# boot.net
KiCad netlist of a schematic drawn in EAGLE
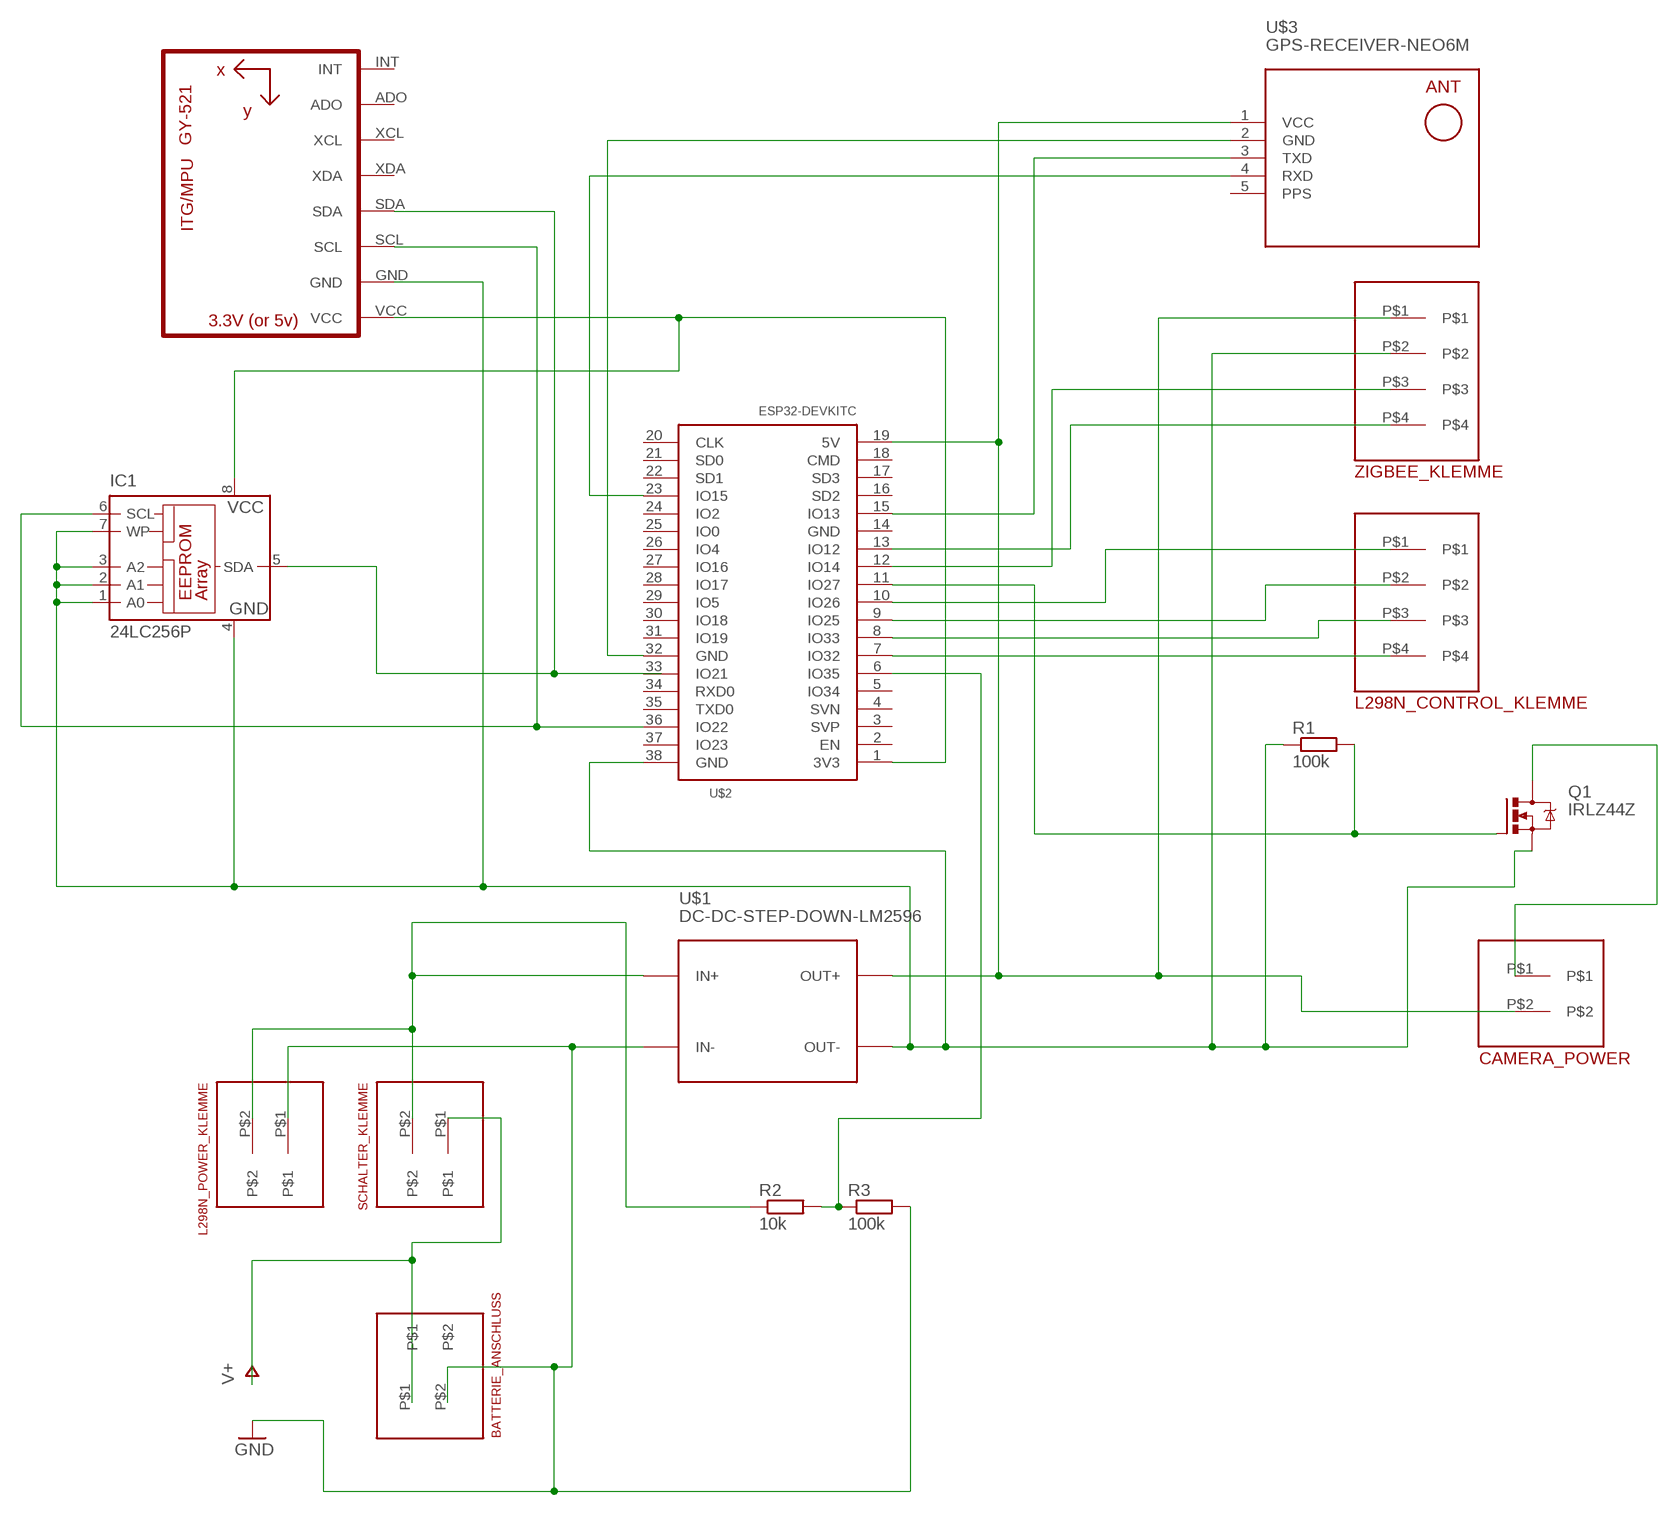
[diagram p0: schematic, sheet 1]

(export (version "E")
  (design (tool "Eeschema 10.0.6"))
  (components
    (comp (ref "BATTERIE_ANSCHLUSS")
      (value "SCHRAUBKLEMME_X_2RM5.08")
      (footprint "eagle-import:2_PIN_RM5.08")
      (libsource (lib "eagle-import") (part "SCHRAUBKLEMME_X_2RM5.08"))
    )
    (comp (ref "CAMERA_POWER")
      (value "AKL_349_X2")
      (footprint "eagle-import:2_PIN_AKL_349_BUCHSE")
      (libsource (lib "eagle-import") (part "AKL_349_X2"))
    )
    (comp (ref "IC1")
      (value "24LC256P")
      (footprint "eagle-import:DIL8")
      (fields (field (name "MF") "MICROCHIP") (field (name "MPN") "24LC256-E/P"))
      (libsource (lib "eagle-import") (part "24PLC256"))
    )
    (comp (ref "L298N_CONTROL_KLEMME")
      (value "SCHRAUBKLEMME_X_4")
      (footprint "eagle-import:4_PIN_RM5.08_SCHRAUBKLEMME")
      (libsource (lib "eagle-import") (part "SCHRAUBKLEMME_X_4"))
    )
    (comp (ref "L298N_POWER_KLEMME")
      (value "SCHRAUBKLEMME_X_2RM5.08")
      (footprint "eagle-import:2_PIN_RM5.08")
      (libsource (lib "eagle-import") (part "SCHRAUBKLEMME_X_2RM5.08"))
    )
    (comp (ref "Q1")
      (value "IRLZ44Z")
      (footprint "eagle-import:TO220BH")
      (libsource (lib "eagle-import") (part "IRLZ44Z"))
    )
    (comp (ref "R1")
      (value "100k")
      (footprint "eagle-import:0207_7")
      (libsource (lib "eagle-import") (part "R-EU_0207/7"))
    )
    (comp (ref "R2")
      (value "10k")
      (footprint "eagle-import:0207_7")
      (libsource (lib "eagle-import") (part "R-EU_0207/7"))
    )
    (comp (ref "R3")
      (value "100k")
      (footprint "eagle-import:0207_7")
      (libsource (lib "eagle-import") (part "R-EU_0207/7"))
    )
    (comp (ref "SCHALTER_KLEMME")
      (value "SCHRAUBKLEMME_X_2RM5.08")
      (footprint "eagle-import:2_PIN_RM5.08")
      (libsource (lib "eagle-import") (part "SCHRAUBKLEMME_X_2RM5.08"))
    )
    (comp (ref "U$1")
      (value "DC-DC-STEP-DOWN-LM2596")
      (footprint "eagle-import:DC-DC-STEP-DOWN-LM2596")
      (libsource (lib "eagle-import") (part "DC-DC-STEP-DOWN-LM2596"))
    )
    (comp (ref "U$2")
      (value "ESP32DEVKITC")
      (footprint "eagle-import:ESP32-DEVKITC")
      (libsource (lib "eagle-import") (part "ESP32DEVKITC"))
    )
    (comp (ref "U$3")
      (value "GPS-RECEIVER-NEO6M")
      (footprint "eagle-import:GPS-RECEIVER-NEO6M")
      (libsource (lib "eagle-import") (part "GPS-RECEIVER-NEO6M"))
    )
    (comp (ref "U1")
      (value "GY-521MPU6050")
      (footprint "eagle-import:GY-521")
      (libsource (lib "eagle-import") (part "GY-521MPU6050"))
    )
    (comp (ref "ZIGBEE_KLEMME")
      (value "SCHRAUBKLEMME_X_4")
      (footprint "eagle-import:4_PIN_RM5.08_SCHRAUBKLEMME")
      (libsource (lib "eagle-import") (part "SCHRAUBKLEMME_X_4"))
    )
  )
  (nets
    (net (code "1") (name "/PPS") (class "Default")
      (node (ref "U$3") (pin "5") (pinfunction "PPS_5") (pintype "power_in"))
    )
    (net (code "2") (name "GND") (class "Default")
      (node (ref "BATTERIE_ANSCHLUSS") (pin "P$2") (pinfunction "P$2_P$2") (pintype "bidirectional"))
      (node (ref "L298N_POWER_KLEMME") (pin "P$1") (pinfunction "P$1_P$1") (pintype "bidirectional"))
      (node (ref "R3") (pin "2") (pinfunction "2_2") (pintype "passive"))
      (node (ref "U$1") (pin "IN-") (pinfunction "IN-_IN-") (pintype "bidirectional"))
    )
    (net (code "3") (name "Net-(CAMERA_POWER-PadP$1)") (class "Default")
      (node (ref "CAMERA_POWER") (pin "P$1") (pinfunction "P$1_P$1") (pintype "bidirectional"))
      (node (ref "Q1") (pin "D") (pinfunction "D_D") (pintype "passive"))
    )
    (net (code "4") (name "Net-(IC1-A0)") (class "Default")
      (node (ref "IC1") (pin "1") (pinfunction "A0_1") (pintype "input"))
      (node (ref "IC1") (pin "2") (pinfunction "A1_2") (pintype "input"))
      (node (ref "IC1") (pin "3") (pinfunction "A2_3") (pintype "input"))
      (node (ref "IC1") (pin "4") (pinfunction "GND_4") (pintype "power_in"))
      (node (ref "IC1") (pin "7") (pinfunction "WP_7") (pintype "input"))
      (node (ref "Q1") (pin "S") (pinfunction "S_S") (pintype "passive"))
      (node (ref "R1") (pin "1") (pinfunction "1_1") (pintype "passive"))
      (node (ref "U$1") (pin "OUT-") (pinfunction "OUT-_OUT-") (pintype "bidirectional"))
      (node (ref "U$2") (pin "38") (pinfunction "GND_38") (pintype "bidirectional"))
      (node (ref "U1") (pin "GND") (pinfunction "GND_GND") (pintype "bidirectional"))
      (node (ref "ZIGBEE_KLEMME") (pin "P$2") (pinfunction "P$2_P$2") (pintype "bidirectional"))
    )
    (net (code "5") (name "Net-(IC1-SCL)") (class "Default")
      (node (ref "IC1") (pin "6") (pinfunction "SCL_6") (pintype "input"))
      (node (ref "U$2") (pin "36") (pinfunction "IO22_36") (pintype "bidirectional"))
      (node (ref "U1") (pin "SCL") (pinfunction "SCL_SCL") (pintype "bidirectional"))
    )
    (net (code "6") (name "Net-(IC1-SDA)") (class "Default")
      (node (ref "IC1") (pin "5") (pinfunction "SDA_5") (pintype "bidirectional"))
      (node (ref "U1") (pin "SDA") (pinfunction "SDA_SDA") (pintype "bidirectional"))
    )
    (net (code "7") (name "Net-(IC1-VCC)") (class "Default")
      (node (ref "IC1") (pin "8") (pinfunction "VCC_8") (pintype "power_in"))
      (node (ref "U$2") (pin "1") (pinfunction "3V3_1") (pintype "bidirectional"))
      (node (ref "U1") (pin "VCC") (pinfunction "VCC_VCC") (pintype "bidirectional"))
    )
    (net (code "8") (name "Net-(L298N_POWER_KLEMME-PadP$2)") (class "Default")
      (node (ref "L298N_POWER_KLEMME") (pin "P$2") (pinfunction "P$2_P$2") (pintype "bidirectional"))
      (node (ref "R2") (pin "1") (pinfunction "1_1") (pintype "passive"))
      (node (ref "SCHALTER_KLEMME") (pin "P$2") (pinfunction "P$2_P$2") (pintype "bidirectional"))
      (node (ref "U$1") (pin "IN+") (pinfunction "IN+_IN+") (pintype "bidirectional"))
    )
    (net (code "9") (name "Net-(U$2-5V)") (class "Default")
      (node (ref "CAMERA_POWER") (pin "P$2") (pinfunction "P$2_P$2") (pintype "bidirectional"))
      (node (ref "U$1") (pin "OUT+") (pinfunction "OUT+_OUT+") (pintype "bidirectional"))
      (node (ref "U$2") (pin "19") (pinfunction "5V_19") (pintype "bidirectional"))
      (node (ref "U$3") (pin "1") (pinfunction "VCC_1") (pintype "bidirectional"))
      (node (ref "ZIGBEE_KLEMME") (pin "P$1") (pinfunction "P$1_P$1") (pintype "bidirectional"))
    )
    (net (code "10") (name "Net-(U$2-IO12)") (class "Default")
      (node (ref "U$2") (pin "13") (pinfunction "IO12_13") (pintype "bidirectional"))
      (node (ref "ZIGBEE_KLEMME") (pin "P$4") (pinfunction "P$4_P$4") (pintype "bidirectional"))
    )
    (net (code "11") (name "Net-(U$2-IO13)") (class "Default")
      (node (ref "U$2") (pin "15") (pinfunction "IO13_15") (pintype "bidirectional"))
      (node (ref "U$3") (pin "3") (pinfunction "TXD_3") (pintype "bidirectional"))
    )
    (net (code "12") (name "Net-(U$2-IO14)") (class "Default")
      (node (ref "U$2") (pin "12") (pinfunction "IO14_12") (pintype "bidirectional"))
      (node (ref "ZIGBEE_KLEMME") (pin "P$3") (pinfunction "P$3_P$3") (pintype "bidirectional"))
    )
    (net (code "13") (name "Net-(U$2-IO15)") (class "Default")
      (node (ref "U$2") (pin "23") (pinfunction "IO15_23") (pintype "bidirectional"))
      (node (ref "U$3") (pin "4") (pinfunction "RXD_4") (pintype "power_in"))
    )
    (net (code "14") (name "Net-(U$2-IO25)") (class "Default")
      (node (ref "L298N_CONTROL_KLEMME") (pin "P$2") (pinfunction "P$2_P$2") (pintype "bidirectional"))
      (node (ref "U$2") (pin "9") (pinfunction "IO25_9") (pintype "bidirectional"))
    )
    (net (code "15") (name "Net-(U$2-IO26)") (class "Default")
      (node (ref "L298N_CONTROL_KLEMME") (pin "P$1") (pinfunction "P$1_P$1") (pintype "bidirectional"))
      (node (ref "U$2") (pin "10") (pinfunction "IO26_10") (pintype "bidirectional"))
    )
    (net (code "16") (name "Net-(U$2-IO27)") (class "Default")
      (node (ref "Q1") (pin "G") (pinfunction "G_G") (pintype "passive"))
      (node (ref "R1") (pin "2") (pinfunction "2_2") (pintype "passive"))
      (node (ref "U$2") (pin "11") (pinfunction "IO27_11") (pintype "bidirectional"))
    )
    (net (code "17") (name "Net-(U$2-IO32)") (class "Default")
      (node (ref "L298N_CONTROL_KLEMME") (pin "P$4") (pinfunction "P$4_P$4") (pintype "bidirectional"))
      (node (ref "U$2") (pin "7") (pinfunction "IO32_7") (pintype "bidirectional"))
    )
    (net (code "18") (name "Net-(U$2-IO33)") (class "Default")
      (node (ref "L298N_CONTROL_KLEMME") (pin "P$3") (pinfunction "P$3_P$3") (pintype "bidirectional"))
      (node (ref "U$2") (pin "8") (pinfunction "IO33_8") (pintype "bidirectional"))
    )
    (net (code "19") (name "Net-(U$2-IO35)") (class "Default")
      (node (ref "R2") (pin "2") (pinfunction "2_2") (pintype "passive"))
      (node (ref "R3") (pin "1") (pinfunction "1_1") (pintype "passive"))
      (node (ref "U$2") (pin "6") (pinfunction "IO35_6") (pintype "bidirectional"))
    )
    (net (code "20") (name "Net-(U$3-GND)") (class "Default")
      (node (ref "U$2") (pin "32") (pinfunction "GND_32") (pintype "bidirectional"))
      (node (ref "U$3") (pin "2") (pinfunction "GND_2") (pintype "bidirectional"))
    )
    (net (code "21") (name "V+") (class "Default")
      (node (ref "BATTERIE_ANSCHLUSS") (pin "P$1") (pinfunction "P$1_P$1") (pintype "bidirectional"))
      (node (ref "SCHALTER_KLEMME") (pin "P$1") (pinfunction "P$1_P$1") (pintype "bidirectional"))
    )
    (net (code "22") (name "unconnected-(U$2-CLK-Pad20)") (class "Default")
      (node (ref "U$2") (pin "20") (pinfunction "CLK_20") (pintype "bidirectional"))
    )
    (net (code "23") (name "unconnected-(U$2-CMD-Pad18)") (class "Default")
      (node (ref "U$2") (pin "18") (pinfunction "CMD_18") (pintype "bidirectional"))
    )
    (net (code "24") (name "unconnected-(U$2-EN-Pad2)") (class "Default")
      (node (ref "U$2") (pin "2") (pinfunction "EN_2") (pintype "bidirectional"))
    )
    (net (code "25") (name "unconnected-(U$2-GND-Pad14)") (class "Default")
      (node (ref "U$2") (pin "14") (pinfunction "GND_14") (pintype "bidirectional"))
    )
    (net (code "26") (name "unconnected-(U$2-IO0-Pad25)") (class "Default")
      (node (ref "U$2") (pin "25") (pinfunction "IO0_25") (pintype "bidirectional"))
    )
    (net (code "27") (name "unconnected-(U$2-IO2-Pad24)") (class "Default")
      (node (ref "U$2") (pin "24") (pinfunction "IO2_24") (pintype "bidirectional"))
    )
    (net (code "28") (name "unconnected-(U$2-IO4-Pad26)") (class "Default")
      (node (ref "U$2") (pin "26") (pinfunction "IO4_26") (pintype "bidirectional"))
    )
    (net (code "29") (name "unconnected-(U$2-IO5-Pad29)") (class "Default")
      (node (ref "U$2") (pin "29") (pinfunction "IO5_29") (pintype "bidirectional"))
    )
    (net (code "30") (name "unconnected-(U$2-IO16-Pad27)") (class "Default")
      (node (ref "U$2") (pin "27") (pinfunction "IO16_27") (pintype "bidirectional"))
    )
    (net (code "31") (name "unconnected-(U$2-IO17-Pad28)") (class "Default")
      (node (ref "U$2") (pin "28") (pinfunction "IO17_28") (pintype "bidirectional"))
    )
    (net (code "32") (name "unconnected-(U$2-IO18-Pad30)") (class "Default")
      (node (ref "U$2") (pin "30") (pinfunction "IO18_30") (pintype "bidirectional"))
    )
    (net (code "33") (name "unconnected-(U$2-IO19-Pad31)") (class "Default")
      (node (ref "U$2") (pin "31") (pinfunction "IO19_31") (pintype "bidirectional"))
    )
    (net (code "34") (name "unconnected-(U$2-IO21-Pad33)") (class "Default")
      (node (ref "U$2") (pin "33") (pinfunction "IO21_33") (pintype "bidirectional"))
    )
    (net (code "35") (name "unconnected-(U$2-IO23-Pad37)") (class "Default")
      (node (ref "U$2") (pin "37") (pinfunction "IO23_37") (pintype "bidirectional"))
    )
    (net (code "36") (name "unconnected-(U$2-IO34-Pad5)") (class "Default")
      (node (ref "U$2") (pin "5") (pinfunction "IO34_5") (pintype "bidirectional"))
    )
    (net (code "37") (name "unconnected-(U$2-RXD0-Pad34)") (class "Default")
      (node (ref "U$2") (pin "34") (pinfunction "RXD0_34") (pintype "bidirectional"))
    )
    (net (code "38") (name "unconnected-(U$2-SD0-Pad21)") (class "Default")
      (node (ref "U$2") (pin "21") (pinfunction "SD0_21") (pintype "bidirectional"))
    )
    (net (code "39") (name "unconnected-(U$2-SD1-Pad22)") (class "Default")
      (node (ref "U$2") (pin "22") (pinfunction "SD1_22") (pintype "bidirectional"))
    )
    (net (code "40") (name "unconnected-(U$2-SD2-Pad16)") (class "Default")
      (node (ref "U$2") (pin "16") (pinfunction "SD2_16") (pintype "bidirectional"))
    )
    (net (code "41") (name "unconnected-(U$2-SD3-Pad17)") (class "Default")
      (node (ref "U$2") (pin "17") (pinfunction "SD3_17") (pintype "bidirectional"))
    )
    (net (code "42") (name "unconnected-(U$2-SVN-Pad4)") (class "Default")
      (node (ref "U$2") (pin "4") (pinfunction "SVN_4") (pintype "bidirectional"))
    )
    (net (code "43") (name "unconnected-(U$2-SVP-Pad3)") (class "Default")
      (node (ref "U$2") (pin "3") (pinfunction "SVP_3") (pintype "bidirectional"))
    )
    (net (code "44") (name "unconnected-(U$2-TXD0-Pad35)") (class "Default")
      (node (ref "U$2") (pin "35") (pinfunction "TXD0_35") (pintype "bidirectional"))
    )
    (net (code "45") (name "unconnected-(U1-PadADO)") (class "Default")
      (node (ref "U1") (pin "ADO") (pinfunction "ADO_ADO") (pintype "bidirectional"))
    )
    (net (code "46") (name "unconnected-(U1-PadINT)") (class "Default")
      (node (ref "U1") (pin "INT") (pinfunction "INT_INT") (pintype "bidirectional"))
    )
    (net (code "47") (name "unconnected-(U1-PadXCL)") (class "Default")
      (node (ref "U1") (pin "XCL") (pinfunction "XCL_XCL") (pintype "bidirectional"))
    )
    (net (code "48") (name "unconnected-(U1-PadXDA)") (class "Default")
      (node (ref "U1") (pin "XDA") (pinfunction "XDA_XDA") (pintype "bidirectional"))
    )
  )
)
